# node_rev_a.net
KiCad netlist of a schematic drawn in EAGLE
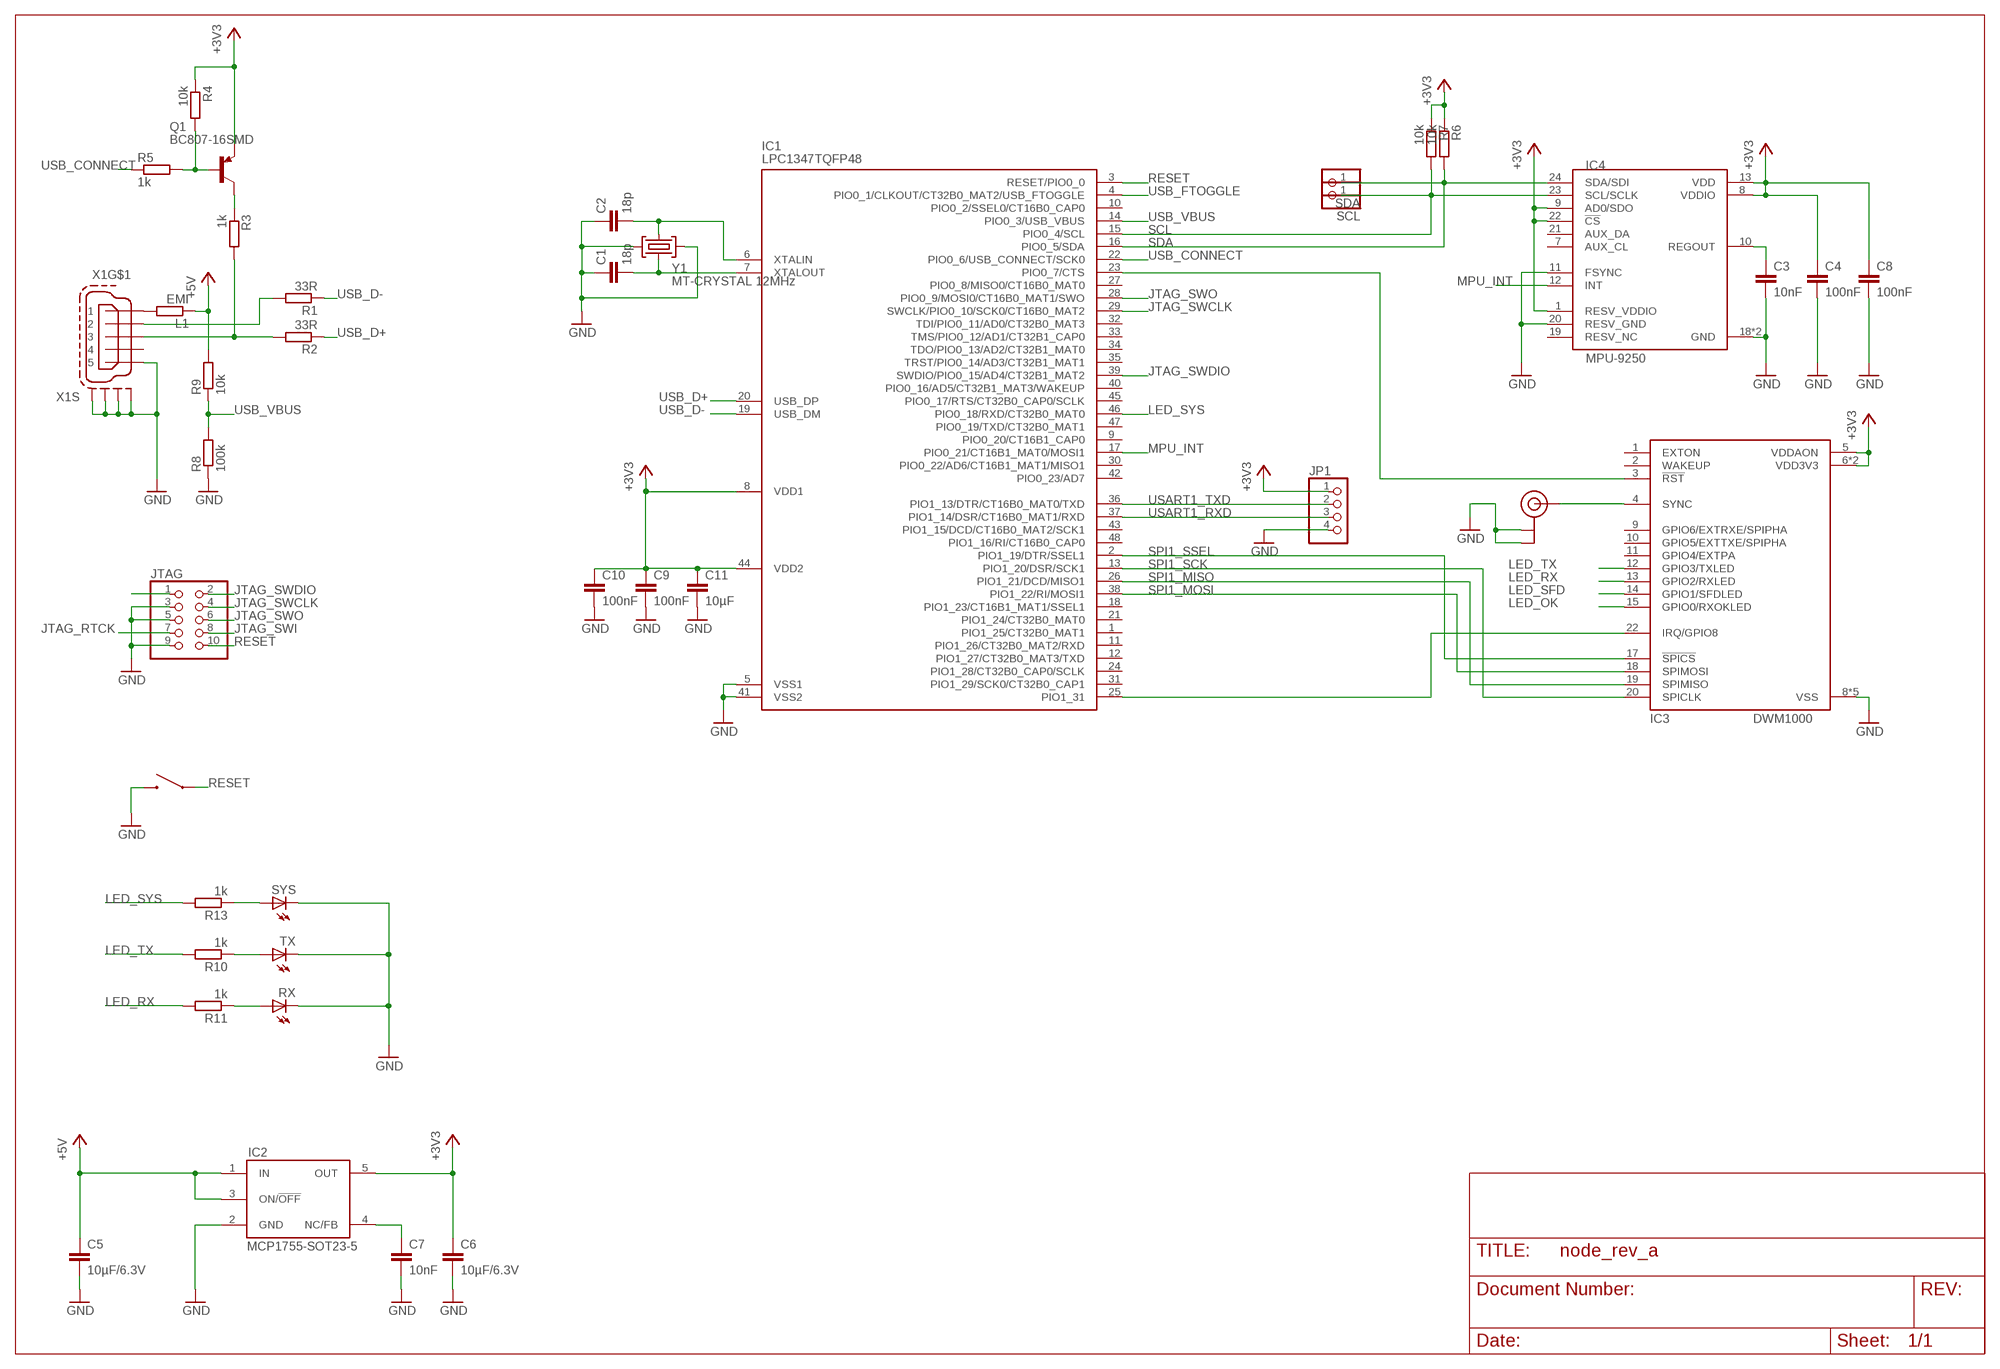
[diagram p0: schematic, sheet 1]

(export (version "E")
  (design (tool "Eeschema 10.0.6"))
  (components
    (comp (ref "C1")
      (value "18p")
      (footprint "eagle-import:C0603")
      (libsource (lib "eagle-import") (part "C-EUC0603"))
    )
    (comp (ref "C2")
      (value "18p")
      (footprint "eagle-import:C0603")
      (libsource (lib "eagle-import") (part "C-EUC0603"))
    )
    (comp (ref "C3")
      (value "10nF")
      (footprint "eagle-import:C0603")
      (libsource (lib "eagle-import") (part "C-EUC0603"))
    )
    (comp (ref "C4")
      (value "100nF")
      (footprint "eagle-import:C0603")
      (libsource (lib "eagle-import") (part "C-EUC0603"))
    )
    (comp (ref "C5")
      (value "10µF/6.3V")
      (footprint "eagle-import:C0603")
      (libsource (lib "eagle-import") (part "C-EUC0603"))
    )
    (comp (ref "C6")
      (value "10µF/6.3V")
      (footprint "eagle-import:C0603")
      (libsource (lib "eagle-import") (part "C-EUC0603"))
    )
    (comp (ref "C7")
      (value "10nF")
      (footprint "eagle-import:C0603")
      (libsource (lib "eagle-import") (part "C-EUC0603"))
    )
    (comp (ref "C8")
      (value "100nF")
      (footprint "eagle-import:C0603")
      (libsource (lib "eagle-import") (part "C-EUC0603"))
    )
    (comp (ref "C9")
      (value "100nF")
      (footprint "eagle-import:C0603")
      (libsource (lib "eagle-import") (part "C-EUC0603"))
    )
    (comp (ref "C10")
      (value "100nF")
      (footprint "eagle-import:C0603")
      (libsource (lib "eagle-import") (part "C-EUC0603"))
    )
    (comp (ref "C11")
      (value "10µF")
      (footprint "eagle-import:C0603")
      (libsource (lib "eagle-import") (part "C-EUC0603"))
    )
    (comp (ref "IC1")
      (value "LPC1347TQFP48")
      (footprint "eagle-import:LQFP48-7X7")
      (libsource (lib "eagle-import") (part "LPC1347TQFP48"))
    )
    (comp (ref "IC2")
      (value "MCP1755-SOT23-5")
      (footprint "eagle-import:SOT23-5")
      (libsource (lib "eagle-import") (part "LP2985-SOT23-5"))
    )
    (comp (ref "IC3")
      (value "DWM1000")
      (footprint "eagle-import:DWM1000")
      (libsource (lib "eagle-import") (part "DWM1000"))
    )
    (comp (ref "IC4")
      (value "MPU-9250")
      (footprint "eagle-import:QFN24_3MM")
      (libsource (lib "eagle-import") (part "MPU-9250"))
    )
    (comp (ref "JP1")
      (value "HEADER-1X4ROUND")
      (footprint "eagle-import:1X04_ROUND")
      (libsource (lib "eagle-import") (part "HEADER-1X4ROUND"))
    )
    (comp (ref "JTAG")
      (value "ARM-JTAG_1.27-SMD")
      (footprint "eagle-import:20021121-10010XXLF")
      (libsource (lib "eagle-import") (part "ARM-JTAG_1.27-SMD"))
    )
    (comp (ref "L1")
      (value "EMI")
      (footprint "eagle-import:R0603")
      (libsource (lib "eagle-import") (part "R-EU_R0603"))
    )
    (comp (ref "Q1")
      (value "BC807-16SMD")
      (footprint "eagle-import:SOT23-BEC")
      (libsource (lib "eagle-import") (part "BC807SMD-16"))
    )
    (comp (ref "R1")
      (value "33R")
      (footprint "eagle-import:R0603")
      (libsource (lib "eagle-import") (part "R-EU_R0603"))
    )
    (comp (ref "R2")
      (value "33R")
      (footprint "eagle-import:R0603")
      (libsource (lib "eagle-import") (part "R-EU_R0603"))
    )
    (comp (ref "R3")
      (value "1k")
      (footprint "eagle-import:R0603")
      (libsource (lib "eagle-import") (part "R-EU_R0603"))
    )
    (comp (ref "R4")
      (value "10k")
      (footprint "eagle-import:R0603")
      (libsource (lib "eagle-import") (part "R-EU_R0603"))
    )
    (comp (ref "R5")
      (value "1k")
      (footprint "eagle-import:R0603")
      (libsource (lib "eagle-import") (part "R-EU_R0603"))
    )
    (comp (ref "R6")
      (value "10k")
      (footprint "eagle-import:R0603")
      (libsource (lib "eagle-import") (part "R-EU_R0603"))
    )
    (comp (ref "R7")
      (value "10k")
      (footprint "eagle-import:R0603")
      (libsource (lib "eagle-import") (part "R-EU_R0603"))
    )
    (comp (ref "R8")
      (value "100k")
      (footprint "eagle-import:R0603")
      (libsource (lib "eagle-import") (part "R-EU_R0603"))
    )
    (comp (ref "R9")
      (value "10k")
      (footprint "eagle-import:R0603")
      (libsource (lib "eagle-import") (part "R-EU_R0603"))
    )
    (comp (ref "R10")
      (value "1k")
      (footprint "eagle-import:R0603")
      (libsource (lib "eagle-import") (part "R-EU_R0603"))
    )
    (comp (ref "R11")
      (value "1k")
      (footprint "eagle-import:R0603")
      (libsource (lib "eagle-import") (part "R-EU_R0603"))
    )
    (comp (ref "R13")
      (value "1k")
      (footprint "eagle-import:R0603")
      (libsource (lib "eagle-import") (part "R-EU_R0603"))
    )
    (comp (ref "RX")
      (value "LEDCHIP-LED0603")
      (footprint "eagle-import:CHIP-LED0603")
      (libsource (lib "eagle-import") (part "LEDCHIP-LED0603"))
    )
    (comp (ref "SCL")
      (value "HEADER-1X12MM")
      (footprint "eagle-import:1X01_2MM")
      (libsource (lib "eagle-import") (part "HEADER-1X12MM"))
    )
    (comp (ref "SDA")
      (value "HEADER-1X12MM")
      (footprint "eagle-import:1X01_2MM")
      (libsource (lib "eagle-import") (part "HEADER-1X12MM"))
    )
    (comp (ref "SYNC")
      (value "U.FL")
      (footprint "eagle-import:U.FL")
      (libsource (lib "eagle-import") (part "U.FL"))
    )
    (comp (ref "SYS")
      (value "LEDCHIP-LED0603")
      (footprint "eagle-import:CHIP-LED0603")
      (libsource (lib "eagle-import") (part "LEDCHIP-LED0603"))
    )
    (comp (ref "TX")
      (value "LEDCHIP-LED0603")
      (footprint "eagle-import:CHIP-LED0603")
      (libsource (lib "eagle-import") (part "LEDCHIP-LED0603"))
    )
    (comp (ref "U$1")
      (value "TACT-SWITCH-40-40")
      (footprint "eagle-import:40-40")
      (libsource (lib "eagle-import") (part "TACT-SWITCH-40-40"))
    )
    (comp (ref "X1")
      (value "MINI-USB-SCHIELD-32005-201")
      (footprint "eagle-import:32005-201")
      (libsource (lib "eagle-import") (part "MINI-USB-SCHIELD-32005-201"))
    )
    (comp (ref "Y1")
      (value "MT-CRYSTAL 12MHz")
      (footprint "eagle-import:MT")
      (libsource (lib "eagle-import") (part "MT-CRYSTAL"))
    )
  )
  (nets
    (net (code "1") (name "+3V3") (class "Default")
      (node (ref "C10") (pin "1") (pinfunction "1_1") (pintype "passive"))
      (node (ref "C11") (pin "1") (pinfunction "1_1") (pintype "passive"))
      (node (ref "C4") (pin "1") (pinfunction "1_1") (pintype "passive"))
      (node (ref "C6") (pin "1") (pinfunction "1_1") (pintype "passive"))
      (node (ref "C8") (pin "1") (pinfunction "1_1") (pintype "passive"))
      (node (ref "C9") (pin "1") (pinfunction "1_1") (pintype "passive"))
      (node (ref "IC1") (pin "44") (pinfunction "VDD2_44") (pintype "bidirectional"))
      (node (ref "IC1") (pin "8") (pinfunction "VDD1_8") (pintype "bidirectional"))
      (node (ref "IC2") (pin "5") (pinfunction "OUT_5") (pintype "bidirectional"))
      (node (ref "IC3") (pin "5") (pinfunction "VDDAON_5") (pintype "bidirectional"))
      (node (ref "IC3") (pin "6") (pinfunction "VDD3V3_6") (pintype "bidirectional"))
      (node (ref "IC3") (pin "7") (pinfunction "VDD3V3_7") (pintype "bidirectional"))
      (node (ref "IC4") (pin "1") (pinfunction "RESV_VDDIO_1") (pintype "bidirectional"))
      (node (ref "IC4") (pin "13") (pinfunction "VDD_13") (pintype "bidirectional"))
      (node (ref "IC4") (pin "22") (pinfunction "~{CS}_22") (pintype "bidirectional"))
      (node (ref "IC4") (pin "8") (pinfunction "VDDIO_8") (pintype "bidirectional"))
      (node (ref "IC4") (pin "9") (pinfunction "AD0/SDO_9") (pintype "bidirectional"))
      (node (ref "JP1") (pin "1") (pinfunction "1_1") (pintype "passive"))
      (node (ref "Q1") (pin "E") (pinfunction "E_E") (pintype "passive"))
      (node (ref "R4") (pin "1") (pinfunction "1_1") (pintype "passive"))
      (node (ref "R6") (pin "1") (pinfunction "1_1") (pintype "passive"))
      (node (ref "R7") (pin "1") (pinfunction "1_1") (pintype "passive"))
    )
    (net (code "2") (name "+5V") (class "Default")
      (node (ref "C5") (pin "1") (pinfunction "1_1") (pintype "passive"))
      (node (ref "IC2") (pin "1") (pinfunction "IN_1") (pintype "bidirectional"))
      (node (ref "IC2") (pin "3") (pinfunction "ON/~{OFF}_3") (pintype "bidirectional"))
      (node (ref "L1") (pin "1") (pinfunction "1_1") (pintype "passive"))
      (node (ref "R9") (pin "2") (pinfunction "2_2") (pintype "passive"))
    )
    (net (code "3") (name "/JTAG_RTCK") (class "Default")
      (node (ref "JTAG") (pin "7") (pinfunction "7_7") (pintype "passive"))
    )
    (net (code "4") (name "/JTAG_SWCLK") (class "Default")
      (node (ref "IC1") (pin "29") (pinfunction "SWCLK/PIO0_10/SCK0/CT16B0_MAT2_29") (pintype "bidirectional"))
      (node (ref "JTAG") (pin "4") (pinfunction "4_4") (pintype "passive"))
    )
    (net (code "5") (name "/JTAG_SWDIO") (class "Default")
      (node (ref "IC1") (pin "39") (pinfunction "SWDIO/PIO0_15/AD4/CT32B1_MAT2_39") (pintype "bidirectional"))
      (node (ref "JTAG") (pin "2") (pinfunction "2_2") (pintype "passive"))
    )
    (net (code "6") (name "/JTAG_SWI") (class "Default")
      (node (ref "JTAG") (pin "8") (pinfunction "8_8") (pintype "passive"))
    )
    (net (code "7") (name "/JTAG_SWO") (class "Default")
      (node (ref "IC1") (pin "28") (pinfunction "PIO0_9/MOSI0/CT16B0_MAT1/SWO_28") (pintype "bidirectional"))
      (node (ref "JTAG") (pin "6") (pinfunction "6_6") (pintype "passive"))
    )
    (net (code "8") (name "/LED_OK") (class "Default")
      (node (ref "IC3") (pin "15") (pinfunction "GPIO0/RXOKLED_15") (pintype "bidirectional"))
    )
    (net (code "9") (name "/LED_RX") (class "Default")
      (node (ref "IC3") (pin "13") (pinfunction "GPIO2/RXLED_13") (pintype "bidirectional"))
      (node (ref "R11") (pin "2") (pinfunction "2_2") (pintype "passive"))
    )
    (net (code "10") (name "/LED_SFD") (class "Default")
      (node (ref "IC3") (pin "14") (pinfunction "GPIO1/SFDLED_14") (pintype "bidirectional"))
    )
    (net (code "11") (name "/LED_SYS") (class "Default")
      (node (ref "IC1") (pin "46") (pinfunction "PIO0_18/RXD/CT32B0_MAT0_46") (pintype "bidirectional"))
      (node (ref "R13") (pin "2") (pinfunction "2_2") (pintype "passive"))
    )
    (net (code "12") (name "/LED_TX") (class "Default")
      (node (ref "IC3") (pin "12") (pinfunction "GPIO3/TXLED_12") (pintype "bidirectional"))
      (node (ref "R10") (pin "2") (pinfunction "2_2") (pintype "passive"))
    )
    (net (code "13") (name "/MPU_INT") (class "Default")
      (node (ref "IC1") (pin "17") (pinfunction "PIO0_21/CT16B1_MAT0/MOSI1_17") (pintype "bidirectional"))
      (node (ref "IC4") (pin "12") (pinfunction "INT_12") (pintype "bidirectional"))
    )
    (net (code "14") (name "/RESET") (class "Default")
      (node (ref "IC1") (pin "3") (pinfunction "RESET/PIO0_0_3") (pintype "bidirectional"))
      (node (ref "JTAG") (pin "10") (pinfunction "10_10") (pintype "passive"))
      (node (ref "U$1") (pin "3") (pinfunction "P$2_3") (pintype "bidirectional"))
      (node (ref "U$1") (pin "4") (pinfunction "P$2_4") (pintype "bidirectional"))
    )
    (net (code "15") (name "/SCL") (class "Default")
      (node (ref "IC1") (pin "15") (pinfunction "PIO0_4/SCL_15") (pintype "bidirectional"))
      (node (ref "IC4") (pin "23") (pinfunction "SCL/SCLK_23") (pintype "bidirectional"))
      (node (ref "R7") (pin "2") (pinfunction "2_2") (pintype "passive"))
      (node (ref "SCL") (pin "1") (pinfunction "1_1") (pintype "passive"))
    )
    (net (code "16") (name "/SDA") (class "Default")
      (node (ref "IC1") (pin "16") (pinfunction "PIO0_5/SDA_16") (pintype "bidirectional"))
      (node (ref "IC4") (pin "24") (pinfunction "SDA/SDI_24") (pintype "bidirectional"))
      (node (ref "R6") (pin "2") (pinfunction "2_2") (pintype "passive"))
      (node (ref "SDA") (pin "1") (pinfunction "1_1") (pintype "passive"))
    )
    (net (code "17") (name "/SPI1_MISO") (class "Default")
      (node (ref "IC1") (pin "26") (pinfunction "PIO1_21/DCD/MISO1_26") (pintype "bidirectional"))
      (node (ref "IC3") (pin "19") (pinfunction "SPIMISO_19") (pintype "bidirectional"))
    )
    (net (code "18") (name "/SPI1_MOSI") (class "Default")
      (node (ref "IC1") (pin "38") (pinfunction "PIO1_22/RI/MOSI1_38") (pintype "bidirectional"))
      (node (ref "IC3") (pin "18") (pinfunction "SPIMOSI_18") (pintype "bidirectional"))
    )
    (net (code "19") (name "/SPI1_SCK") (class "Default")
      (node (ref "IC1") (pin "13") (pinfunction "PIO1_20/DSR/SCK1_13") (pintype "bidirectional"))
      (node (ref "IC3") (pin "20") (pinfunction "SPICLK_20") (pintype "bidirectional"))
    )
    (net (code "20") (name "/SPI1_SSEL") (class "Default")
      (node (ref "IC1") (pin "2") (pinfunction "PIO1_19/DTR/SSEL1_2") (pintype "bidirectional"))
      (node (ref "IC3") (pin "17") (pinfunction "~{SPICS}_17") (pintype "bidirectional"))
    )
    (net (code "21") (name "/USART1_RXD") (class "Default")
      (node (ref "IC1") (pin "37") (pinfunction "PIO1_14/DSR/CT16B0_MAT1/RXD_37") (pintype "bidirectional"))
      (node (ref "JP1") (pin "3") (pinfunction "3_3") (pintype "passive"))
    )
    (net (code "22") (name "/USART1_TXD") (class "Default")
      (node (ref "IC1") (pin "36") (pinfunction "PIO1_13/DTR/CT16B0_MAT0/TXD_36") (pintype "bidirectional"))
      (node (ref "JP1") (pin "2") (pinfunction "2_2") (pintype "passive"))
    )
    (net (code "23") (name "/USB_CONNECT") (class "Default")
      (node (ref "IC1") (pin "22") (pinfunction "PIO0_6/USB_CONNECT/SCK0_22") (pintype "bidirectional"))
      (node (ref "R5") (pin "1") (pinfunction "1_1") (pintype "passive"))
    )
    (net (code "24") (name "/USB_D+") (class "Default")
      (node (ref "IC1") (pin "20") (pinfunction "USB_DP_20") (pintype "bidirectional"))
      (node (ref "R2") (pin "1") (pinfunction "1_1") (pintype "passive"))
    )
    (net (code "25") (name "/USB_D-") (class "Default")
      (node (ref "IC1") (pin "19") (pinfunction "USB_DM_19") (pintype "bidirectional"))
      (node (ref "R1") (pin "1") (pinfunction "1_1") (pintype "passive"))
    )
    (net (code "26") (name "/USB_FTOGGLE") (class "Default")
      (node (ref "IC1") (pin "4") (pinfunction "PIO0_1/CLKOUT/CT32B0_MAT2/USB_FTOGGLE_4") (pintype "bidirectional"))
    )
    (net (code "27") (name "/USB_VBUS") (class "Default")
      (node (ref "IC1") (pin "14") (pinfunction "PIO0_3/USB_VBUS_14") (pintype "bidirectional"))
      (node (ref "R8") (pin "2") (pinfunction "2_2") (pintype "passive"))
      (node (ref "R9") (pin "1") (pinfunction "1_1") (pintype "passive"))
    )
    (net (code "28") (name "GND") (class "Default")
      (node (ref "C1") (pin "1") (pinfunction "1_1") (pintype "passive"))
      (node (ref "C10") (pin "2") (pinfunction "2_2") (pintype "passive"))
      (node (ref "C11") (pin "2") (pinfunction "2_2") (pintype "passive"))
      (node (ref "C2") (pin "1") (pinfunction "1_1") (pintype "passive"))
      (node (ref "C3") (pin "2") (pinfunction "2_2") (pintype "passive"))
      (node (ref "C4") (pin "2") (pinfunction "2_2") (pintype "passive"))
      (node (ref "C5") (pin "2") (pinfunction "2_2") (pintype "passive"))
      (node (ref "C6") (pin "2") (pinfunction "2_2") (pintype "passive"))
      (node (ref "C7") (pin "2") (pinfunction "2_2") (pintype "passive"))
      (node (ref "C8") (pin "2") (pinfunction "2_2") (pintype "passive"))
      (node (ref "C9") (pin "2") (pinfunction "2_2") (pintype "passive"))
      (node (ref "IC1") (pin "41") (pinfunction "VSS2_41") (pintype "bidirectional"))
      (node (ref "IC1") (pin "5") (pinfunction "VSS1_5") (pintype "bidirectional"))
      (node (ref "IC2") (pin "2") (pinfunction "GND_2") (pintype "bidirectional"))
      (node (ref "IC3") (pin "16") (pinfunction "VSS_16") (pintype "bidirectional"))
      (node (ref "IC3") (pin "21") (pinfunction "VSS_21") (pintype "bidirectional"))
      (node (ref "IC3") (pin "23") (pinfunction "VSS_23") (pintype "bidirectional"))
      (node (ref "IC3") (pin "24") (pinfunction "VSS_24") (pintype "bidirectional"))
      (node (ref "IC3") (pin "8") (pinfunction "VSS_8") (pintype "bidirectional"))
      (node (ref "IC4") (pin "11") (pinfunction "FSYNC_11") (pintype "bidirectional"))
      (node (ref "IC4") (pin "18") (pinfunction "GND_18") (pintype "bidirectional"))
      (node (ref "IC4") (pin "20") (pinfunction "RESV_GND_20") (pintype "bidirectional"))
      (node (ref "IC4") (pin "THERM") (pinfunction "GND_THERM") (pintype "bidirectional"))
      (node (ref "JP1") (pin "4") (pinfunction "4_4") (pintype "passive"))
      (node (ref "JTAG") (pin "3") (pinfunction "3_3") (pintype "passive"))
      (node (ref "JTAG") (pin "5") (pinfunction "5_5") (pintype "passive"))
      (node (ref "JTAG") (pin "9") (pinfunction "9_9") (pintype "passive"))
      (node (ref "R8") (pin "1") (pinfunction "1_1") (pintype "passive"))
      (node (ref "RX") (pin "C") (pinfunction "C_C") (pintype "passive"))
      (node (ref "SYNC") (pin "1") (pinfunction "GND_1") (pintype "passive"))
      (node (ref "SYNC") (pin "2") (pinfunction "GND_2") (pintype "passive"))
      (node (ref "SYS") (pin "C") (pinfunction "C_C") (pintype "passive"))
      (node (ref "TX") (pin "C") (pinfunction "C_C") (pintype "passive"))
      (node (ref "U$1") (pin "1") (pinfunction "P$1_1") (pintype "bidirectional"))
      (node (ref "U$1") (pin "2") (pinfunction "P$1_2") (pintype "bidirectional"))
      (node (ref "X1") (pin "5") (pinfunction "5_5") (pintype "passive"))
      (node (ref "X1") (pin "M1") (pinfunction "S1_M1") (pintype "passive"))
      (node (ref "X1") (pin "M2") (pinfunction "S2_M2") (pintype "passive"))
      (node (ref "X1") (pin "M3") (pinfunction "S3_M3") (pintype "passive"))
      (node (ref "X1") (pin "M4") (pinfunction "S4_M4") (pintype "passive"))
      (node (ref "Y1") (pin "2") (pinfunction "GND2_2") (pintype "bidirectional"))
      (node (ref "Y1") (pin "4") (pinfunction "GND1_4") (pintype "bidirectional"))
    )
    (net (code "29") (name "Net-(IC1-PIO0_7{slash}CTS)") (class "Default")
      (node (ref "IC1") (pin "23") (pinfunction "PIO0_7/CTS_23") (pintype "bidirectional"))
      (node (ref "IC3") (pin "3") (pinfunction "~{RST}_3") (pintype "bidirectional"))
    )
    (net (code "30") (name "Net-(IC1-PIO1_31)") (class "Default")
      (node (ref "IC1") (pin "25") (pinfunction "PIO1_31_25") (pintype "bidirectional"))
      (node (ref "IC3") (pin "22") (pinfunction "IRQ/GPIO8_22") (pintype "bidirectional"))
    )
    (net (code "31") (name "Net-(IC1-XTALIN)") (class "Default")
      (node (ref "C2") (pin "2") (pinfunction "2_2") (pintype "passive"))
      (node (ref "IC1") (pin "6") (pinfunction "XTALIN_6") (pintype "bidirectional"))
      (node (ref "Y1") (pin "1") (pinfunction "CRYSTAL2_1") (pintype "bidirectional"))
    )
    (net (code "32") (name "Net-(IC1-XTALOUT)") (class "Default")
      (node (ref "C1") (pin "2") (pinfunction "2_2") (pintype "passive"))
      (node (ref "IC1") (pin "7") (pinfunction "XTALOUT_7") (pintype "bidirectional"))
      (node (ref "Y1") (pin "3") (pinfunction "CRYSTAL1_3") (pintype "bidirectional"))
    )
    (net (code "33") (name "Net-(IC2-NC{slash}FB)") (class "Default")
      (node (ref "C7") (pin "1") (pinfunction "1_1") (pintype "passive"))
      (node (ref "IC2") (pin "4") (pinfunction "NC/FB_4") (pintype "bidirectional"))
    )
    (net (code "34") (name "Net-(IC3-SYNC)") (class "Default")
      (node (ref "IC3") (pin "4") (pinfunction "SYNC_4") (pintype "bidirectional"))
      (node (ref "SYNC") (pin "3") (pinfunction "SIGNAL_3") (pintype "passive"))
    )
    (net (code "35") (name "Net-(IC4-REGOUT)") (class "Default")
      (node (ref "C3") (pin "1") (pinfunction "1_1") (pintype "passive"))
      (node (ref "IC4") (pin "10") (pinfunction "REGOUT_10") (pintype "bidirectional"))
    )
    (net (code "36") (name "Net-(L1-Pad2)") (class "Default")
      (node (ref "L1") (pin "2") (pinfunction "2_2") (pintype "passive"))
      (node (ref "X1") (pin "1") (pinfunction "1_1") (pintype "passive"))
    )
    (net (code "37") (name "Net-(Q1-PadB)") (class "Default")
      (node (ref "Q1") (pin "B") (pinfunction "B_B") (pintype "passive"))
      (node (ref "R4") (pin "2") (pinfunction "2_2") (pintype "passive"))
      (node (ref "R5") (pin "2") (pinfunction "2_2") (pintype "passive"))
    )
    (net (code "38") (name "Net-(Q1-PadC)") (class "Default")
      (node (ref "Q1") (pin "C") (pinfunction "C_C") (pintype "passive"))
      (node (ref "R3") (pin "1") (pinfunction "1_1") (pintype "passive"))
    )
    (net (code "39") (name "Net-(R1-Pad2)") (class "Default")
      (node (ref "R1") (pin "2") (pinfunction "2_2") (pintype "passive"))
      (node (ref "X1") (pin "2") (pinfunction "2_2") (pintype "passive"))
    )
    (net (code "40") (name "Net-(R2-Pad2)") (class "Default")
      (node (ref "R2") (pin "2") (pinfunction "2_2") (pintype "passive"))
      (node (ref "R3") (pin "2") (pinfunction "2_2") (pintype "passive"))
      (node (ref "X1") (pin "3") (pinfunction "3_3") (pintype "passive"))
    )
    (net (code "41") (name "Net-(R10-Pad1)") (class "Default")
      (node (ref "R10") (pin "1") (pinfunction "1_1") (pintype "passive"))
      (node (ref "TX") (pin "A") (pinfunction "A_A") (pintype "passive"))
    )
    (net (code "42") (name "Net-(R11-Pad1)") (class "Default")
      (node (ref "R11") (pin "1") (pinfunction "1_1") (pintype "passive"))
      (node (ref "RX") (pin "A") (pinfunction "A_A") (pintype "passive"))
    )
    (net (code "43") (name "Net-(R13-Pad1)") (class "Default")
      (node (ref "R13") (pin "1") (pinfunction "1_1") (pintype "passive"))
      (node (ref "SYS") (pin "A") (pinfunction "A_A") (pintype "passive"))
    )
    (net (code "44") (name "unconnected-(IC1-PIO0_2{slash}SSEL0{slash}CT16B0_CAP0-Pad10)") (class "Default")
      (node (ref "IC1") (pin "10") (pinfunction "PIO0_2/SSEL0/CT16B0_CAP0_10") (pintype "bidirectional"))
    )
    (net (code "45") (name "unconnected-(IC1-PIO0_8{slash}MISO0{slash}CT16B0_MAT0-Pad27)") (class "Default")
      (node (ref "IC1") (pin "27") (pinfunction "PIO0_8/MISO0/CT16B0_MAT0_27") (pintype "bidirectional"))
    )
    (net (code "46") (name "unconnected-(IC1-PIO0_16{slash}AD5{slash}CT32B1_MAT3{slash}WAKEUP-Pad40)") (class "Default")
      (node (ref "IC1") (pin "40") (pinfunction "PIO0_16/AD5/CT32B1_MAT3/WAKEUP_40") (pintype "bidirectional"))
    )
    (net (code "47") (name "unconnected-(IC1-PIO0_17{slash}RTS{slash}CT32B0_CAP0{slash}SCLK-Pad45)") (class "Default")
      (node (ref "IC1") (pin "45") (pinfunction "PIO0_17/RTS/CT32B0_CAP0/SCLK_45") (pintype "bidirectional"))
    )
    (net (code "48") (name "unconnected-(IC1-PIO0_19{slash}TXD{slash}CT32B0_MAT1-Pad47)") (class "Default")
      (node (ref "IC1") (pin "47") (pinfunction "PIO0_19/TXD/CT32B0_MAT1_47") (pintype "bidirectional"))
    )
    (net (code "49") (name "unconnected-(IC1-PIO0_20{slash}CT16B1_CAP0-Pad9)") (class "Default")
      (node (ref "IC1") (pin "9") (pinfunction "PIO0_20/CT16B1_CAP0_9") (pintype "bidirectional"))
    )
    (net (code "50") (name "unconnected-(IC1-PIO0_22{slash}AD6{slash}CT16B1_MAT1{slash}MISO1-Pad30)") (class "Default")
      (node (ref "IC1") (pin "30") (pinfunction "PIO0_22/AD6/CT16B1_MAT1/MISO1_30") (pintype "bidirectional"))
    )
    (net (code "51") (name "unconnected-(IC1-PIO0_23{slash}AD7-Pad42)") (class "Default")
      (node (ref "IC1") (pin "42") (pinfunction "PIO0_23/AD7_42") (pintype "bidirectional"))
    )
    (net (code "52") (name "unconnected-(IC1-PIO1_15{slash}DCD{slash}CT16B0_MAT2{slash}SCK1-Pad43)") (class "Default")
      (node (ref "IC1") (pin "43") (pinfunction "PIO1_15/DCD/CT16B0_MAT2/SCK1_43") (pintype "bidirectional"))
    )
    (net (code "53") (name "unconnected-(IC1-PIO1_16{slash}RI{slash}CT16B0_CAP0-Pad48)") (class "Default")
      (node (ref "IC1") (pin "48") (pinfunction "PIO1_16/RI/CT16B0_CAP0_48") (pintype "bidirectional"))
    )
    (net (code "54") (name "unconnected-(IC1-PIO1_23{slash}CT16B1_MAT1{slash}SSEL1-Pad18)") (class "Default")
      (node (ref "IC1") (pin "18") (pinfunction "PIO1_23/CT16B1_MAT1/SSEL1_18") (pintype "bidirectional"))
    )
    (net (code "55") (name "unconnected-(IC1-PIO1_24{slash}CT32B0_MAT0-Pad21)") (class "Default")
      (node (ref "IC1") (pin "21") (pinfunction "PIO1_24/CT32B0_MAT0_21") (pintype "bidirectional"))
    )
    (net (code "56") (name "unconnected-(IC1-PIO1_25{slash}CT32B0_MAT1-Pad1)") (class "Default")
      (node (ref "IC1") (pin "1") (pinfunction "PIO1_25/CT32B0_MAT1_1") (pintype "bidirectional"))
    )
    (net (code "57") (name "unconnected-(IC1-PIO1_26{slash}CT32B0_MAT2{slash}RXD-Pad11)") (class "Default")
      (node (ref "IC1") (pin "11") (pinfunction "PIO1_26/CT32B0_MAT2/RXD_11") (pintype "bidirectional"))
    )
    (net (code "58") (name "unconnected-(IC1-PIO1_27{slash}CT32B0_MAT3{slash}TXD-Pad12)") (class "Default")
      (node (ref "IC1") (pin "12") (pinfunction "PIO1_27/CT32B0_MAT3/TXD_12") (pintype "bidirectional"))
    )
    (net (code "59") (name "unconnected-(IC1-PIO1_28{slash}CT32B0_CAP0{slash}SCLK-Pad24)") (class "Default")
      (node (ref "IC1") (pin "24") (pinfunction "PIO1_28/CT32B0_CAP0/SCLK_24") (pintype "bidirectional"))
    )
    (net (code "60") (name "unconnected-(IC1-PIO1_29{slash}SCK0{slash}CT32B0_CAP1-Pad31)") (class "Default")
      (node (ref "IC1") (pin "31") (pinfunction "PIO1_29/SCK0/CT32B0_CAP1_31") (pintype "bidirectional"))
    )
    (net (code "61") (name "unconnected-(IC1-TDI{slash}PIO0_11{slash}AD0{slash}CT32B0_MAT3-Pad32)") (class "Default")
      (node (ref "IC1") (pin "32") (pinfunction "TDI/PIO0_11/AD0/CT32B0_MAT3_32") (pintype "bidirectional"))
    )
    (net (code "62") (name "unconnected-(IC1-TDO{slash}PIO0_13{slash}AD2{slash}CT32B1_MAT0-Pad34)") (class "Default")
      (node (ref "IC1") (pin "34") (pinfunction "TDO/PIO0_13/AD2/CT32B1_MAT0_34") (pintype "bidirectional"))
    )
    (net (code "63") (name "unconnected-(IC1-TMS{slash}PIO0_12{slash}AD1{slash}CT32B1_CAP0-Pad33)") (class "Default")
      (node (ref "IC1") (pin "33") (pinfunction "TMS/PIO0_12/AD1/CT32B1_CAP0_33") (pintype "bidirectional"))
    )
    (net (code "64") (name "unconnected-(IC1-TRST{slash}PIO0_14{slash}AD3{slash}CT32B1_MAT1-Pad35)") (class "Default")
      (node (ref "IC1") (pin "35") (pinfunction "TRST/PIO0_14/AD3/CT32B1_MAT1_35") (pintype "bidirectional"))
    )
    (net (code "65") (name "unconnected-(IC3-EXTON-Pad1)") (class "Default")
      (node (ref "IC3") (pin "1") (pinfunction "EXTON_1") (pintype "bidirectional"))
    )
    (net (code "66") (name "unconnected-(IC3-GPIO4{slash}EXTPA-Pad11)") (class "Default")
      (node (ref "IC3") (pin "11") (pinfunction "GPIO4/EXTPA_11") (pintype "bidirectional"))
    )
    (net (code "67") (name "unconnected-(IC3-GPIO5{slash}EXTTXE{slash}SPIPHA-Pad10)") (class "Default")
      (node (ref "IC3") (pin "10") (pinfunction "GPIO5/EXTTXE/SPIPHA_10") (pintype "bidirectional"))
    )
    (net (code "68") (name "unconnected-(IC3-GPIO6{slash}EXTRXE{slash}SPIPHA-Pad9)") (class "Default")
      (node (ref "IC3") (pin "9") (pinfunction "GPIO6/EXTRXE/SPIPHA_9") (pintype "bidirectional"))
    )
    (net (code "69") (name "unconnected-(IC3-WAKEUP-Pad2)") (class "Default")
      (node (ref "IC3") (pin "2") (pinfunction "WAKEUP_2") (pintype "bidirectional"))
    )
    (net (code "70") (name "unconnected-(IC4-AUX_CL-Pad7)") (class "Default")
      (node (ref "IC4") (pin "7") (pinfunction "AUX_CL_7") (pintype "bidirectional"))
    )
    (net (code "71") (name "unconnected-(IC4-AUX_DA-Pad21)") (class "Default")
      (node (ref "IC4") (pin "21") (pinfunction "AUX_DA_21") (pintype "bidirectional"))
    )
    (net (code "72") (name "unconnected-(IC4-RESV_NC-Pad19)") (class "Default")
      (node (ref "IC4") (pin "19") (pinfunction "RESV_NC_19") (pintype "bidirectional"))
    )
    (net (code "73") (name "unconnected-(JTAG-Pad1)") (class "Default")
      (node (ref "JTAG") (pin "1") (pinfunction "1_1") (pintype "passive"))
    )
    (net (code "74") (name "unconnected-(X1-Pad4)") (class "Default")
      (node (ref "X1") (pin "4") (pinfunction "4_4") (pintype "passive"))
    )
  )
)
